# 3_waffling60-DB_mcu.net
KiCad netlist of a schematic drawn in Altium Designer
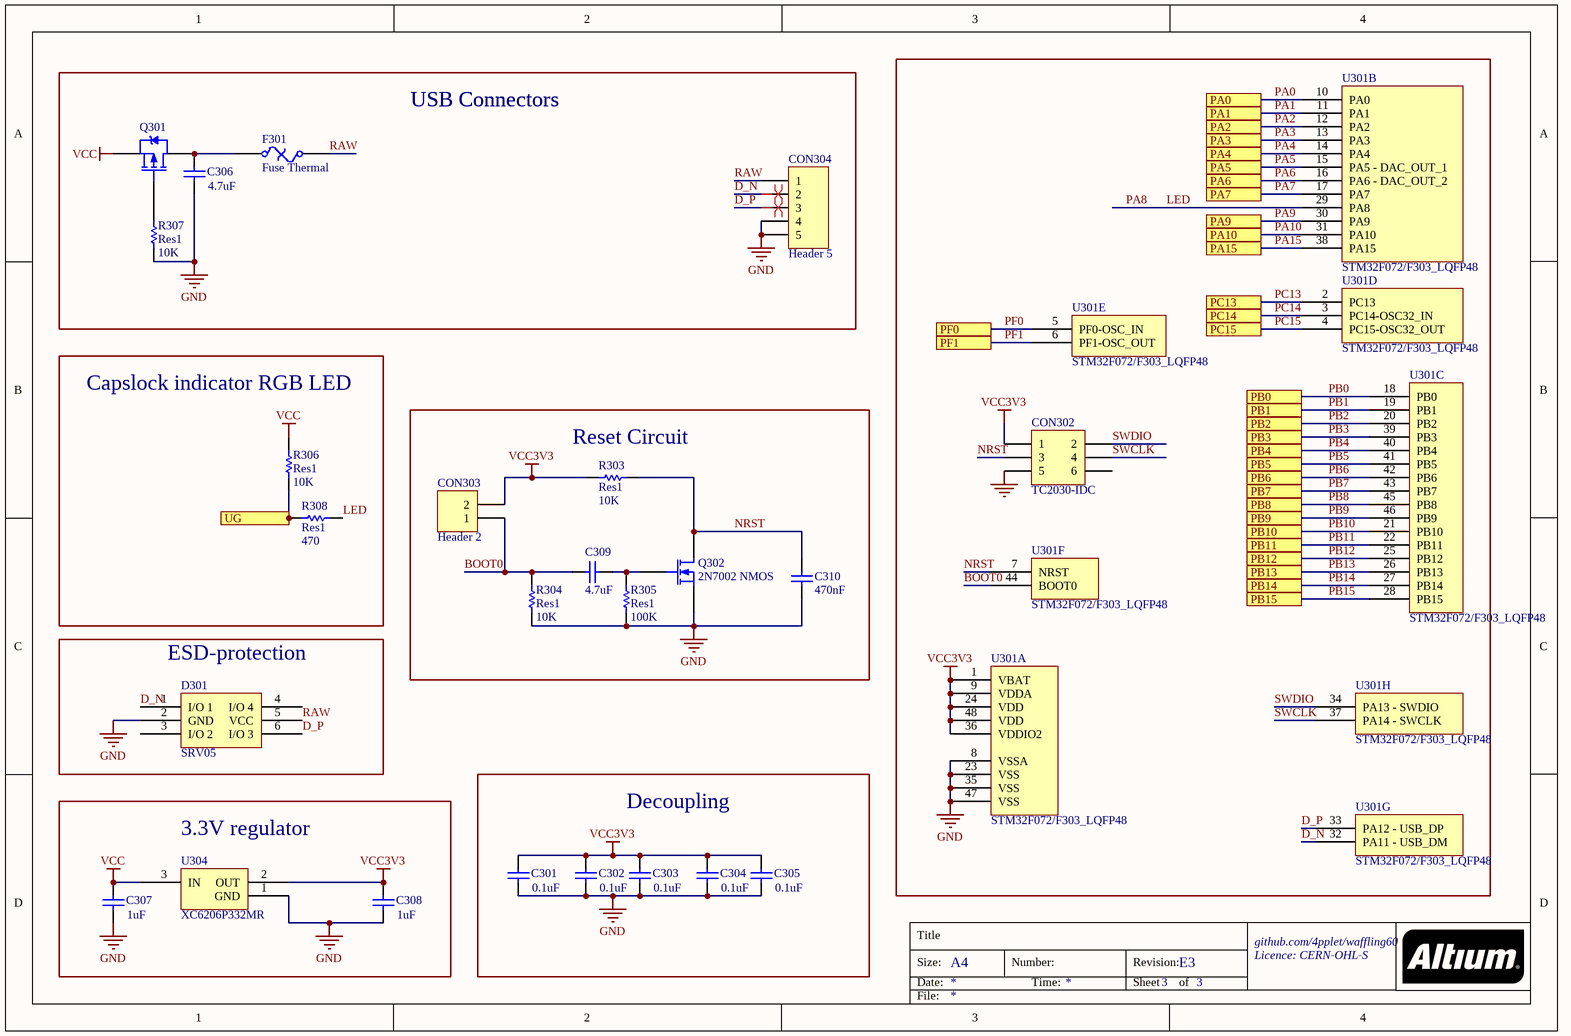
[diagram p0: 3_waffling60-DB_mcu.SchDoc]

(export (version "E")
  (design (tool "Eeschema 10.0.6"))
  (components
    (comp (ref "C301")
      (value "0.1uF")
      (footprint "C0603[1608]")
      (description "Capacitor")
      (fields (field (name "LCSC PART #") "C14663") (field (name "MRF.PART") "CC0603KRX7R9BB104"))
      (libsource (lib "Miscellaneous Devices") (part "Cap"))
    )
    (comp (ref "C302")
      (value "0.1uF")
      (footprint "C0603[1608]")
      (description "Capacitor")
      (fields (field (name "LCSC PART #") "C14663") (field (name "MRF.PART") "CC0603KRX7R9BB104"))
      (libsource (lib "Miscellaneous Devices") (part "Cap"))
    )
    (comp (ref "C303")
      (value "0.1uF")
      (footprint "C0603[1608]")
      (description "Capacitor")
      (fields (field (name "LCSC PART #") "C14663") (field (name "MRF.PART") "CC0603KRX7R9BB104"))
      (libsource (lib "Miscellaneous Devices") (part "Cap"))
    )
    (comp (ref "C304")
      (value "0.1uF")
      (footprint "C0603[1608]")
      (description "Capacitor")
      (fields (field (name "LCSC PART #") "C14663") (field (name "MRF.PART") "CC0603KRX7R9BB104"))
      (libsource (lib "Miscellaneous Devices") (part "Cap"))
    )
    (comp (ref "C305")
      (value "0.1uF")
      (footprint "C0603[1608]")
      (description "Capacitor")
      (fields (field (name "LCSC PART #") "C14663") (field (name "MRF.PART") "CC0603KRX7R9BB104"))
      (libsource (lib "Miscellaneous Devices") (part "Cap"))
    )
    (comp (ref "C306")
      (value "4.7uF")
      (footprint "C0603[1608]")
      (description "Capacitor")
      (fields (field (name "LCSC PART #") "C19666") (field (name "MRF.PART") "CL10A475KO8NNNC"))
      (libsource (lib "Miscellaneous Devices") (part "Cap"))
    )
    (comp (ref "C307")
      (value "1uF")
      (footprint "C0603[1608]")
      (description "Capacitor")
      (fields (field (name "LCSC PART #") "C15849") (field (name "MRF.PART") "CL10A105KB8NNNC"))
      (libsource (lib "Miscellaneous Devices") (part "Cap"))
    )
    (comp (ref "C308")
      (value "1uF")
      (footprint "C0603[1608]")
      (description "Capacitor")
      (fields (field (name "LCSC PART #") "C15849") (field (name "MRF.PART") "CL10A105KB8NNNC"))
      (libsource (lib "Miscellaneous Devices") (part "Cap"))
    )
    (comp (ref "C309")
      (value "4.7uF")
      (footprint "C0603[1608]")
      (description "Capacitor")
      (fields (field (name "LCSC PART #") "C19666") (field (name "MRF.PART") "CL10A475KO8NNNC"))
      (libsource (lib "Miscellaneous Devices") (part "Cap"))
    )
    (comp (ref "C310")
      (value "470nF")
      (footprint "C0603[1608]")
      (description "Capacitor")
      (fields (field (name "LCSC PART #") "C1623") (field (name "MRF.PART") "CL10B474KA8NNNC"))
      (libsource (lib "Miscellaneous Devices") (part "Cap"))
    )
    (comp (ref "CON302")
      (value "TC2030-IDC")
      (footprint "TC2030-IDC-NL")
      (description "Header, 3-Pin, Dual row")
      (libsource (lib "Miscellaneous Connectors") (part "Header 3X2"))
    )
    (comp (ref "CON303")
      (value "Header 2")
      (footprint "HDR1X2")
      (description "Header, 2-Pin")
      (libsource (lib "Miscellaneous Connectors") (part "Header 2"))
    )
    (comp (ref "CON304")
      (value "Header 5")
      (footprint "UDB_combo_JST_MOLEX")
      (description "JST for USB daughter board")
      (fields (field (name "LCSC PART #") "C145956"))
      (libsource (lib "Miscellaneous Connectors") (part "Header 5"))
    )
    (comp (ref "D301")
      (value "SRV05")
      (footprint "SOT-23-6")
      (fields (field (name "LCSC PART #") "C85364") (field (name "MRF.PART") "SRV05-4-P-T7"))
      (libsource (lib "Keebs") (part "SRV05"))
    )
    (comp (ref "F301")
      (value "Fuse Thermal")
      (footprint "C1206[3216]")
      (description "Thermal Fuse")
      (fields (field (name "LCSC PART #") "C135338") (field (name "MRF.PART") "ASMD1206-050"))
      (libsource (lib "Miscellaneous Devices") (part "Fuse Thermal"))
    )
    (comp (ref "Q301")
      (value "PMOS-2")
      (footprint "SOT-23-3")
      (description "P-Channel Power MOSFET")
      (fields (field (name "LCSC PART #") "C10487") (field (name "MRF.PART") "SI2301CDS-T1-GE3"))
      (libsource (lib "Miscellaneous Devices") (part "PMOS-2"))
    )
    (comp (ref "Q302")
      (value "2N7002 NMOS")
      (footprint "SOT-23-3")
      (description "N-Channel MOSFET")
      (fields (field (name "LCSC PART #") "C8545") (field (name "MRF.PART") "2N7002"))
      (libsource (lib "Miscellaneous Devices") (part "MOSFET-N"))
    )
    (comp (ref "R303")
      (value "Res1")
      (footprint "R0603[1608]")
      (description "Resistor")
      (fields
        (field (name "ALTIUM_VALUE") "10K")
        (field (name "LCSC PART #") "C25804")
        (field (name "MRF.PART") "0603WAF1002T5E")
      )
      (libsource (lib "Miscellaneous Devices") (part "Res1"))
    )
    (comp (ref "R304")
      (value "Res1")
      (footprint "R0603[1608]")
      (description "Resistor")
      (fields
        (field (name "ALTIUM_VALUE") "10K")
        (field (name "LCSC PART #") "C25804")
        (field (name "MRF.PART") "0603WAF1002T5E")
      )
      (libsource (lib "Miscellaneous Devices") (part "Res1"))
    )
    (comp (ref "R305")
      (value "Res1")
      (footprint "R0603[1608]")
      (description "Resistor")
      (fields
        (field (name "ALTIUM_VALUE") "100K")
        (field (name "LCSC PART #") "C25803")
        (field (name "MRF.PART") "0603WAF1003T5E")
      )
      (libsource (lib "Miscellaneous Devices") (part "Res1"))
    )
    (comp (ref "R306")
      (value "Res1")
      (footprint "R0603[1608]")
      (description "Resistor")
      (fields
        (field (name "ALTIUM_VALUE") "10K")
        (field (name "LCSC PART #") "C25804")
        (field (name "MRF.PART") "0603WAF1002T5E")
      )
      (libsource (lib "Miscellaneous Devices") (part "Res1"))
    )
    (comp (ref "R307")
      (value "Res1")
      (footprint "R0603[1608]")
      (description "Resistor")
      (fields
        (field (name "ALTIUM_VALUE") "10K")
        (field (name "LCSC PART #") "C25804")
        (field (name "MRF.PART") "0603WAF1002T5E")
      )
      (libsource (lib "Miscellaneous Devices") (part "Res1"))
    )
    (comp (ref "R308")
      (value "Res1")
      (footprint "R0603[1608]")
      (description "Resistor")
      (fields
        (field (name "ALTIUM_VALUE") "470")
        (field (name "LCSC PART #") "C23179")
        (field (name "MRF.PART") "0603WAF4700T5E")
      )
      (libsource (lib "Miscellaneous Devices") (part "Res1"))
    )
    (comp (ref "U301")
      (value "STM32F072/F303_LQFP48")
      (footprint "STM32 - COMBO 7X7MM")
      (fields (field (name "LCSC PART #") "C915660") (field (name "MRF.PART") "APM32F072CBT6"))
      (libsource (lib "Keebs") (part "STM32F072/F303_LQFP48"))
    )
    (comp (ref "U304")
      (value "XC6206P332MR")
      (footprint "SOT-23-3")
      (fields (field (name "LCSC PART #") "C5446"))
      (libsource (lib "Keebs") (part "SOT23 LDO"))
    )
  )
  (nets
    (net (code "1") (name "/BOOT0") (class "Default")
      (node (ref "C309") (pin "1") (pinfunction "1_1") (pintype "passive"))
      (node (ref "CON303") (pin "1") (pinfunction "1_1") (pintype "passive"))
      (node (ref "R304") (pin "1") (pinfunction "1_1") (pintype "passive"))
      (node (ref "U301") (pin "44") (pinfunction "BOOT0_44") (pintype "passive"))
    )
    (net (code "2") (name "/D_N") (class "Default")
      (node (ref "CON304") (pin "2") (pinfunction "2_2") (pintype "passive"))
      (node (ref "D301") (pin "1") (pinfunction "I/O_1_1") (pintype "passive"))
      (node (ref "U301") (pin "32") (pinfunction "PA11_-_USB_DM_32") (pintype "passive"))
    )
    (net (code "3") (name "/D_P") (class "Default")
      (node (ref "CON304") (pin "3") (pinfunction "3_3") (pintype "passive"))
      (node (ref "D301") (pin "6") (pinfunction "I/O_3_6") (pintype "passive"))
      (node (ref "U301") (pin "33") (pinfunction "PA12_-_USB_DP_33") (pintype "passive"))
    )
    (net (code "4") (name "/LED") (class "Default")
      (node (ref "R308") (pin "2") (pinfunction "2_2") (pintype "passive"))
      (node (ref "U301") (pin "29") (pinfunction "PA8_29") (pintype "passive"))
    )
    (net (code "5") (name "/NRST") (class "Default")
      (node (ref "C310") (pin "1") (pinfunction "1_1") (pintype "passive"))
      (node (ref "CON302") (pin "3") (pinfunction "3_3") (pintype "passive"))
      (node (ref "Q302") (pin "3") (pinfunction "D_3") (pintype "passive"))
      (node (ref "R303") (pin "2") (pinfunction "2_2") (pintype "passive"))
      (node (ref "U301") (pin "7") (pinfunction "NRST_7") (pintype "passive"))
    )
    (net (code "6") (name "/PA0") (class "Default")
      (node (ref "U301") (pin "10") (pinfunction "PA0_10") (pintype "passive"))
    )
    (net (code "7") (name "/PA1") (class "Default")
      (node (ref "U301") (pin "11") (pinfunction "PA1_11") (pintype "passive"))
    )
    (net (code "8") (name "/PA2") (class "Default")
      (node (ref "U301") (pin "12") (pinfunction "PA2_12") (pintype "passive"))
    )
    (net (code "9") (name "/PA3") (class "Default")
      (node (ref "U301") (pin "13") (pinfunction "PA3_13") (pintype "passive"))
    )
    (net (code "10") (name "/PA4") (class "Default")
      (node (ref "U301") (pin "14") (pinfunction "PA4_14") (pintype "passive"))
    )
    (net (code "11") (name "/PA5") (class "Default")
      (node (ref "U301") (pin "15") (pinfunction "PA5_-_DAC_OUT_1_15") (pintype "passive"))
    )
    (net (code "12") (name "/PA6") (class "Default")
      (node (ref "U301") (pin "16") (pinfunction "PA6_-_DAC_OUT_2_16") (pintype "passive"))
    )
    (net (code "13") (name "/PA7") (class "Default")
      (node (ref "U301") (pin "17") (pinfunction "PA7_17") (pintype "passive"))
    )
    (net (code "14") (name "/PA9") (class "Default")
      (node (ref "U301") (pin "30") (pinfunction "PA9_30") (pintype "passive"))
    )
    (net (code "15") (name "/PA10") (class "Default")
      (node (ref "U301") (pin "31") (pinfunction "PA10_31") (pintype "passive"))
    )
    (net (code "16") (name "/PA15") (class "Default")
      (node (ref "U301") (pin "38") (pinfunction "PA15_38") (pintype "passive"))
    )
    (net (code "17") (name "/PB0") (class "Default")
      (node (ref "U301") (pin "18") (pinfunction "PB0_18") (pintype "passive"))
    )
    (net (code "18") (name "/PB1") (class "Default")
      (node (ref "U301") (pin "19") (pinfunction "PB1_19") (pintype "passive"))
    )
    (net (code "19") (name "/PB2") (class "Default")
      (node (ref "U301") (pin "20") (pinfunction "PB2_20") (pintype "passive"))
    )
    (net (code "20") (name "/PB3") (class "Default")
      (node (ref "U301") (pin "39") (pinfunction "PB3_39") (pintype "passive"))
    )
    (net (code "21") (name "/PB4") (class "Default")
      (node (ref "U301") (pin "40") (pinfunction "PB4_40") (pintype "passive"))
    )
    (net (code "22") (name "/PB5") (class "Default")
      (node (ref "U301") (pin "41") (pinfunction "PB5_41") (pintype "passive"))
    )
    (net (code "23") (name "/PB6") (class "Default")
      (node (ref "U301") (pin "42") (pinfunction "PB6_42") (pintype "passive"))
    )
    (net (code "24") (name "/PB7") (class "Default")
      (node (ref "U301") (pin "43") (pinfunction "PB7_43") (pintype "passive"))
    )
    (net (code "25") (name "/PB8") (class "Default")
      (node (ref "U301") (pin "45") (pinfunction "PB8_45") (pintype "passive"))
    )
    (net (code "26") (name "/PB9") (class "Default")
      (node (ref "U301") (pin "46") (pinfunction "PB9_46") (pintype "passive"))
    )
    (net (code "27") (name "/PB10") (class "Default")
      (node (ref "U301") (pin "21") (pinfunction "PB10_21") (pintype "passive"))
    )
    (net (code "28") (name "/PB11") (class "Default")
      (node (ref "U301") (pin "22") (pinfunction "PB11_22") (pintype "passive"))
    )
    (net (code "29") (name "/PB12") (class "Default")
      (node (ref "U301") (pin "25") (pinfunction "PB12_25") (pintype "passive"))
    )
    (net (code "30") (name "/PB13") (class "Default")
      (node (ref "U301") (pin "26") (pinfunction "PB13_26") (pintype "passive"))
    )
    (net (code "31") (name "/PB14") (class "Default")
      (node (ref "U301") (pin "27") (pinfunction "PB14_27") (pintype "passive"))
    )
    (net (code "32") (name "/PB15") (class "Default")
      (node (ref "U301") (pin "28") (pinfunction "PB15_28") (pintype "passive"))
    )
    (net (code "33") (name "/PC13") (class "Default")
      (node (ref "U301") (pin "2") (pinfunction "PC13_2") (pintype "passive"))
    )
    (net (code "34") (name "/PC14") (class "Default")
      (node (ref "U301") (pin "3") (pinfunction "PC14-OSC32_IN_3") (pintype "passive"))
    )
    (net (code "35") (name "/PC15") (class "Default")
      (node (ref "U301") (pin "4") (pinfunction "PC15-OSC32_OUT_4") (pintype "passive"))
    )
    (net (code "36") (name "/PF0") (class "Default")
      (node (ref "U301") (pin "5") (pinfunction "PF0-OSC_IN_5") (pintype "passive"))
    )
    (net (code "37") (name "/PF1") (class "Default")
      (node (ref "U301") (pin "6") (pinfunction "PF1-OSC_OUT_6") (pintype "passive"))
    )
    (net (code "38") (name "/RAW") (class "Default")
      (node (ref "CON304") (pin "1") (pinfunction "1_1") (pintype "passive"))
      (node (ref "D301") (pin "5") (pinfunction "VCC_5") (pintype "passive"))
      (node (ref "F301") (pin "2") (pinfunction "2_2") (pintype "passive"))
    )
    (net (code "39") (name "/SWCLK") (class "Default")
      (node (ref "CON302") (pin "4") (pinfunction "4_4") (pintype "passive"))
      (node (ref "U301") (pin "37") (pinfunction "PA14_-_SWCLK_37") (pintype "passive"))
    )
    (net (code "40") (name "/SWDIO") (class "Default")
      (node (ref "CON302") (pin "2") (pinfunction "2_2") (pintype "passive"))
      (node (ref "U301") (pin "34") (pinfunction "PA13_-_SWDIO_34") (pintype "passive"))
    )
    (net (code "41") (name "/UG") (class "Default")
      (node (ref "R306") (pin "2") (pinfunction "2_2") (pintype "passive"))
      (node (ref "R308") (pin "1") (pinfunction "1_1") (pintype "passive"))
    )
    (net (code "42") (name "GND") (class "Default")
      (node (ref "C301") (pin "1") (pinfunction "1_1") (pintype "passive"))
      (node (ref "C302") (pin "1") (pinfunction "1_1") (pintype "passive"))
      (node (ref "C303") (pin "1") (pinfunction "1_1") (pintype "passive"))
      (node (ref "C304") (pin "1") (pinfunction "1_1") (pintype "passive"))
      (node (ref "C305") (pin "1") (pinfunction "1_1") (pintype "passive"))
      (node (ref "C306") (pin "1") (pinfunction "1_1") (pintype "passive"))
      (node (ref "C307") (pin "1") (pinfunction "1_1") (pintype "passive"))
      (node (ref "C308") (pin "1") (pinfunction "1_1") (pintype "passive"))
      (node (ref "C310") (pin "2") (pinfunction "2_2") (pintype "passive"))
      (node (ref "CON302") (pin "5") (pinfunction "5_5") (pintype "passive"))
      (node (ref "CON304") (pin "4") (pinfunction "4_4") (pintype "passive"))
      (node (ref "CON304") (pin "5") (pinfunction "5_5") (pintype "passive"))
      (node (ref "D301") (pin "2") (pinfunction "GND_2") (pintype "passive"))
      (node (ref "Q302") (pin "2") (pinfunction "S_2") (pintype "passive"))
      (node (ref "R304") (pin "2") (pinfunction "2_2") (pintype "passive"))
      (node (ref "R305") (pin "2") (pinfunction "2_2") (pintype "passive"))
      (node (ref "R307") (pin "2") (pinfunction "2_2") (pintype "passive"))
      (node (ref "U301") (pin "23") (pinfunction "VSS_23") (pintype "passive"))
      (node (ref "U301") (pin "35") (pinfunction "VSS_35") (pintype "passive"))
      (node (ref "U301") (pin "47") (pinfunction "VSS_47") (pintype "passive"))
      (node (ref "U301") (pin "8") (pinfunction "VSSA_8") (pintype "passive"))
      (node (ref "U304") (pin "1") (pinfunction "GND_1") (pintype "passive"))
    )
    (net (code "43") (name "Net-(Q301-D)") (class "Default")
      (node (ref "C306") (pin "2") (pinfunction "2_2") (pintype "passive"))
      (node (ref "F301") (pin "1") (pinfunction "1_1") (pintype "passive"))
      (node (ref "Q301") (pin "3") (pinfunction "D_3") (pintype "passive"))
    )
    (net (code "44") (name "Net-(Q301-G)") (class "Default")
      (node (ref "Q301") (pin "1") (pinfunction "G_1") (pintype "passive"))
      (node (ref "R307") (pin "1") (pinfunction "1_1") (pintype "passive"))
    )
    (net (code "45") (name "Net-(Q302-G)") (class "Default")
      (node (ref "C309") (pin "2") (pinfunction "2_2") (pintype "passive"))
      (node (ref "Q302") (pin "1") (pinfunction "G_1") (pintype "passive"))
      (node (ref "R305") (pin "1") (pinfunction "1_1") (pintype "passive"))
    )
    (net (code "46") (name "VCC") (class "Default")
      (node (ref "C307") (pin "2") (pinfunction "2_2") (pintype "passive"))
      (node (ref "Q301") (pin "2") (pinfunction "S_2") (pintype "passive"))
      (node (ref "R306") (pin "1") (pinfunction "1_1") (pintype "passive"))
      (node (ref "U304") (pin "3") (pinfunction "IN_3") (pintype "passive"))
    )
    (net (code "47") (name "VCC3V3") (class "Default")
      (node (ref "C301") (pin "2") (pinfunction "2_2") (pintype "passive"))
      (node (ref "C302") (pin "2") (pinfunction "2_2") (pintype "passive"))
      (node (ref "C303") (pin "2") (pinfunction "2_2") (pintype "passive"))
      (node (ref "C304") (pin "2") (pinfunction "2_2") (pintype "passive"))
      (node (ref "C305") (pin "2") (pinfunction "2_2") (pintype "passive"))
      (node (ref "C308") (pin "2") (pinfunction "2_2") (pintype "passive"))
      (node (ref "CON302") (pin "1") (pinfunction "1_1") (pintype "passive"))
      (node (ref "CON303") (pin "2") (pinfunction "2_2") (pintype "passive"))
      (node (ref "R303") (pin "1") (pinfunction "1_1") (pintype "passive"))
      (node (ref "U301") (pin "1") (pinfunction "VBAT_1") (pintype "passive"))
      (node (ref "U301") (pin "24") (pinfunction "VDD_24") (pintype "passive"))
      (node (ref "U301") (pin "36") (pinfunction "VDDIO2_36") (pintype "passive"))
      (node (ref "U301") (pin "48") (pinfunction "VDD_48") (pintype "passive"))
      (node (ref "U301") (pin "9") (pinfunction "VDDA_9") (pintype "passive"))
      (node (ref "U304") (pin "2") (pinfunction "OUT_2") (pintype "passive"))
    )
    (net (code "48") (name "unconnected-(CON302-Pad6)") (class "Default")
      (node (ref "CON302") (pin "6") (pinfunction "6_6") (pintype "passive"))
    )
    (net (code "49") (name "unconnected-(D301-I{slash}O_2-Pad3)") (class "Default")
      (node (ref "D301") (pin "3") (pinfunction "I/O_2_3") (pintype "passive"))
    )
    (net (code "50") (name "unconnected-(D301-I{slash}O_4-Pad4)") (class "Default")
      (node (ref "D301") (pin "4") (pinfunction "I/O_4_4") (pintype "passive"))
    )
  )
)
